# untitled.net
KiCad netlist of a schematic drawn in EAGLE
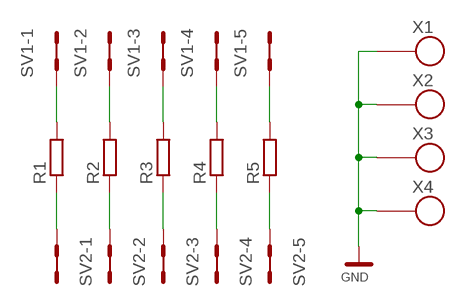
[diagram p0: schematic, sheet 1]

(export (version "E")
  (design (tool "Eeschema 10.0.6"))
  (components
    (comp (ref "R1")
      (value "R0805")
      (footprint "eagle-import:0805")
      (libsource (lib "eagle-import") (part "R0805"))
    )
    (comp (ref "R2")
      (value "R0805")
      (footprint "eagle-import:0805")
      (libsource (lib "eagle-import") (part "R0805"))
    )
    (comp (ref "R3")
      (value "R0805")
      (footprint "eagle-import:0805")
      (libsource (lib "eagle-import") (part "R0805"))
    )
    (comp (ref "R4")
      (value "R0805")
      (footprint "eagle-import:0805")
      (libsource (lib "eagle-import") (part "R0805"))
    )
    (comp (ref "R5")
      (value "R0805")
      (footprint "eagle-import:0805")
      (libsource (lib "eagle-import") (part "R0805"))
    )
    (comp (ref "SV1")
      (value "MA05-2")
      (footprint "eagle-import:MA05-2")
      (libsource (lib "eagle-import") (part "MA05-2"))
    )
    (comp (ref "SV2")
      (value "MA05-2")
      (footprint "eagle-import:MA05-2")
      (libsource (lib "eagle-import") (part "MA05-2"))
    )
    (comp (ref "X1")
      (value "SROUB3M")
      (footprint "eagle-import:SROUB3M")
      (libsource (lib "eagle-import") (part "SROUB3M"))
    )
    (comp (ref "X2")
      (value "SROUB3M")
      (footprint "eagle-import:SROUB3M")
      (libsource (lib "eagle-import") (part "SROUB3M"))
    )
    (comp (ref "X3")
      (value "SROUB3M")
      (footprint "eagle-import:SROUB3M")
      (libsource (lib "eagle-import") (part "SROUB3M"))
    )
    (comp (ref "X4")
      (value "SROUB3M")
      (footprint "eagle-import:SROUB3M")
      (libsource (lib "eagle-import") (part "SROUB3M"))
    )
  )
  (nets
    (net (code "1") (name "GND") (class "Default")
      (node (ref "X1") (pin "P$1") (pinfunction "P$1_P$1") (pintype "bidirectional"))
      (node (ref "X2") (pin "P$1") (pinfunction "P$1_P$1") (pintype "bidirectional"))
      (node (ref "X3") (pin "P$1") (pinfunction "P$1_P$1") (pintype "bidirectional"))
      (node (ref "X4") (pin "P$1") (pinfunction "P$1_P$1") (pintype "bidirectional"))
    )
    (net (code "2") (name "Net-(R1-Pad1)") (class "Default")
      (node (ref "R1") (pin "1") (pinfunction "1_1") (pintype "passive"))
      (node (ref "SV2") (pin "1") (pinfunction "K_1") (pintype "passive"))
      (node (ref "SV2") (pin "2") (pinfunction "K_2") (pintype "passive"))
    )
    (net (code "3") (name "Net-(R1-Pad2)") (class "Default")
      (node (ref "R1") (pin "2") (pinfunction "2_2") (pintype "passive"))
      (node (ref "SV1") (pin "1") (pinfunction "K_1") (pintype "passive"))
      (node (ref "SV1") (pin "2") (pinfunction "K_2") (pintype "passive"))
    )
    (net (code "4") (name "Net-(R2-Pad1)") (class "Default")
      (node (ref "R2") (pin "1") (pinfunction "1_1") (pintype "passive"))
      (node (ref "SV2") (pin "3") (pinfunction "K_3") (pintype "passive"))
      (node (ref "SV2") (pin "4") (pinfunction "K_4") (pintype "passive"))
    )
    (net (code "5") (name "Net-(R2-Pad2)") (class "Default")
      (node (ref "R2") (pin "2") (pinfunction "2_2") (pintype "passive"))
      (node (ref "SV1") (pin "3") (pinfunction "K_3") (pintype "passive"))
      (node (ref "SV1") (pin "4") (pinfunction "K_4") (pintype "passive"))
    )
    (net (code "6") (name "Net-(R3-Pad1)") (class "Default")
      (node (ref "R3") (pin "1") (pinfunction "1_1") (pintype "passive"))
      (node (ref "SV2") (pin "5") (pinfunction "K_5") (pintype "passive"))
      (node (ref "SV2") (pin "6") (pinfunction "K_6") (pintype "passive"))
    )
    (net (code "7") (name "Net-(R3-Pad2)") (class "Default")
      (node (ref "R3") (pin "2") (pinfunction "2_2") (pintype "passive"))
      (node (ref "SV1") (pin "5") (pinfunction "K_5") (pintype "passive"))
      (node (ref "SV1") (pin "6") (pinfunction "K_6") (pintype "passive"))
    )
    (net (code "8") (name "Net-(R4-Pad1)") (class "Default")
      (node (ref "R4") (pin "1") (pinfunction "1_1") (pintype "passive"))
      (node (ref "SV2") (pin "7") (pinfunction "K_7") (pintype "passive"))
      (node (ref "SV2") (pin "8") (pinfunction "K_8") (pintype "passive"))
    )
    (net (code "9") (name "Net-(R4-Pad2)") (class "Default")
      (node (ref "R4") (pin "2") (pinfunction "2_2") (pintype "passive"))
      (node (ref "SV1") (pin "7") (pinfunction "K_7") (pintype "passive"))
      (node (ref "SV1") (pin "8") (pinfunction "K_8") (pintype "passive"))
    )
    (net (code "10") (name "Net-(R5-Pad1)") (class "Default")
      (node (ref "R5") (pin "1") (pinfunction "1_1") (pintype "passive"))
      (node (ref "SV2") (pin "10") (pinfunction "K_10") (pintype "passive"))
      (node (ref "SV2") (pin "9") (pinfunction "K_9") (pintype "passive"))
    )
    (net (code "11") (name "Net-(R5-Pad2)") (class "Default")
      (node (ref "R5") (pin "2") (pinfunction "2_2") (pintype "passive"))
      (node (ref "SV1") (pin "10") (pinfunction "K_10") (pintype "passive"))
      (node (ref "SV1") (pin "9") (pinfunction "K_9") (pintype "passive"))
    )
  )
)
